# k26_baseboard_telemetry_extconn.net
KiCad netlist of a schematic drawn in Altium Designer
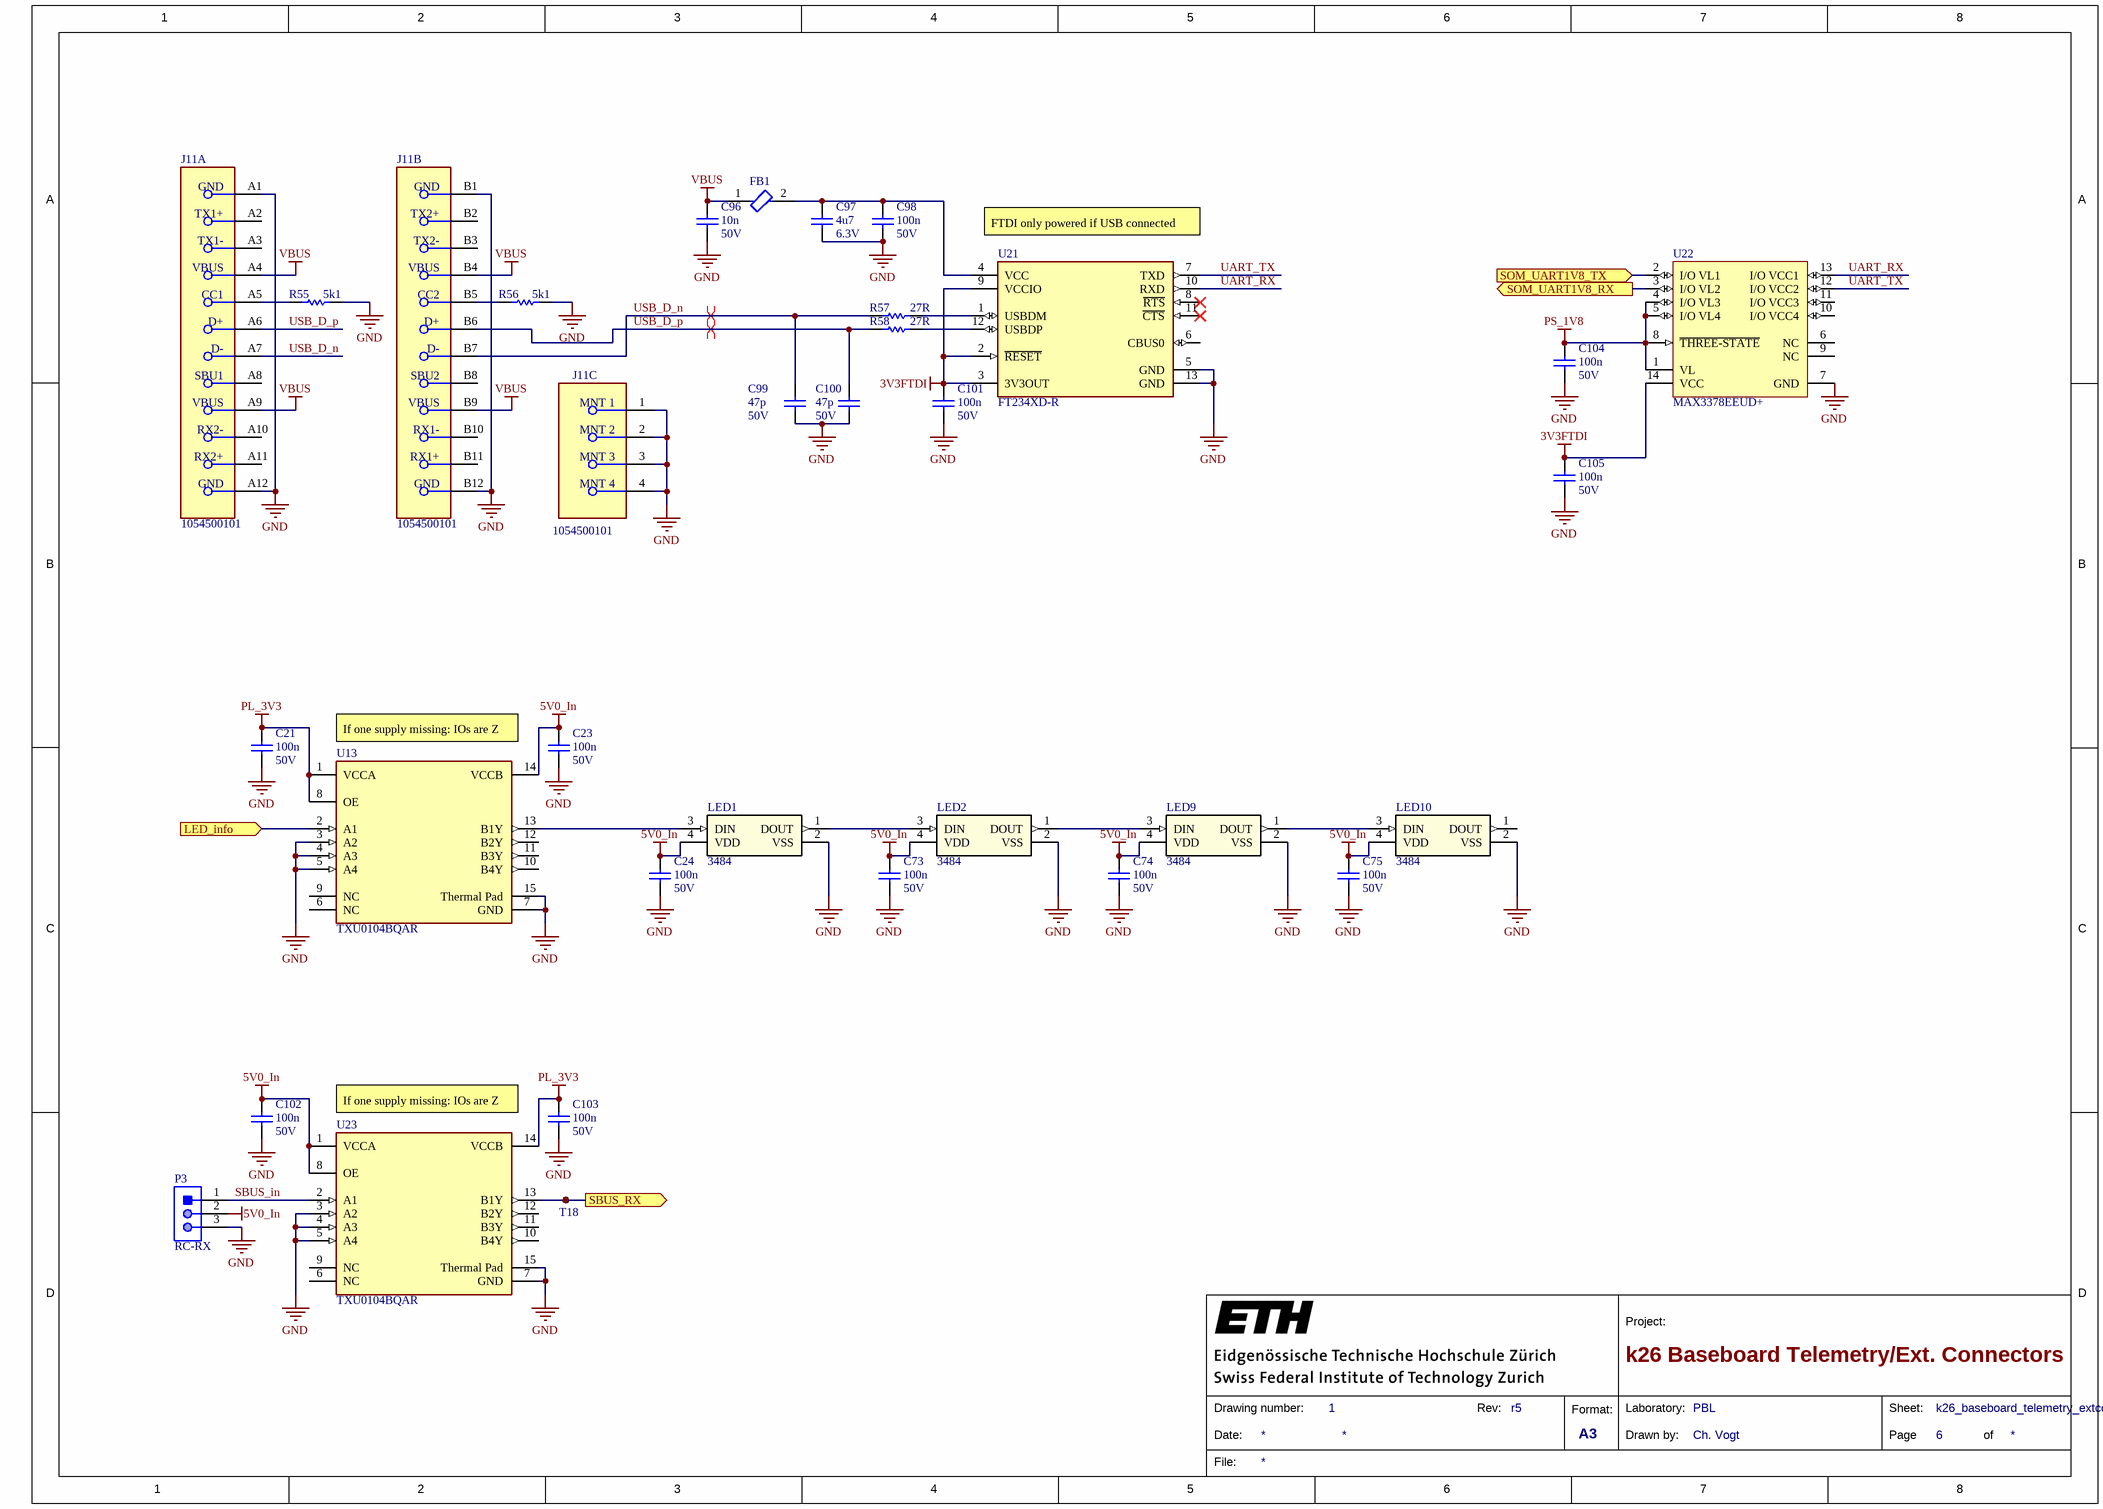
[diagram p0: k26_baseboard_telemetry_extconn.SchDoc]

(export (version "E")
  (design (tool "Eeschema 10.0.6"))
  (components
    (comp (ref "C21")
      (value "100n")
      (footprint "k26_FPGA_drone_baseboard:CAPC0402")
      (fields
        (field (name "MANUFACTURER") "Yageo")
        (field (name "MANUFACTURER PART NUMBER") "CC0402KRX5R9BB104")
        (field (name "RATED DC VOLTAGE (URDC)") "50V")
      )
      (libsource (lib "k26_FPGA_drone_baseboard") (part "cap0402"))
    )
    (comp (ref "C23")
      (value "100n")
      (footprint "k26_FPGA_drone_baseboard:CAPC0402")
      (fields
        (field (name "MANUFACTURER") "Yageo")
        (field (name "MANUFACTURER PART NUMBER") "CC0402KRX5R9BB104")
        (field (name "RATED DC VOLTAGE (URDC)") "50V")
      )
      (libsource (lib "k26_FPGA_drone_baseboard") (part "cap0402"))
    )
    (comp (ref "C24")
      (value "100n")
      (footprint "k26_FPGA_drone_baseboard:CAPC0402")
      (fields
        (field (name "MANUFACTURER") "Yageo")
        (field (name "MANUFACTURER PART NUMBER") "CC0402KRX5R9BB104")
        (field (name "RATED DC VOLTAGE (URDC)") "50V")
      )
      (libsource (lib "k26_FPGA_drone_baseboard") (part "cap0402"))
    )
    (comp (ref "C73")
      (value "100n")
      (footprint "k26_FPGA_drone_baseboard:CAPC0402")
      (fields
        (field (name "MANUFACTURER") "Yageo")
        (field (name "MANUFACTURER PART NUMBER") "CC0402KRX5R9BB104")
        (field (name "RATED DC VOLTAGE (URDC)") "50V")
      )
      (libsource (lib "k26_FPGA_drone_baseboard") (part "cap0402"))
    )
    (comp (ref "C74")
      (value "100n")
      (footprint "k26_FPGA_drone_baseboard:CAPC0402")
      (fields
        (field (name "MANUFACTURER") "Yageo")
        (field (name "MANUFACTURER PART NUMBER") "CC0402KRX5R9BB104")
        (field (name "RATED DC VOLTAGE (URDC)") "50V")
      )
      (libsource (lib "k26_FPGA_drone_baseboard") (part "cap0402"))
    )
    (comp (ref "C75")
      (value "100n")
      (footprint "k26_FPGA_drone_baseboard:CAPC0402")
      (fields
        (field (name "MANUFACTURER") "Yageo")
        (field (name "MANUFACTURER PART NUMBER") "CC0402KRX5R9BB104")
        (field (name "RATED DC VOLTAGE (URDC)") "50V")
      )
      (libsource (lib "k26_FPGA_drone_baseboard") (part "cap0402"))
    )
    (comp (ref "C96")
      (value "10n")
      (footprint "k26_FPGA_drone_baseboard:CAPC0402")
      (fields
        (field (name "MANUFACTURER") "Samsung")
        (field (name "MANUFACTURER PART NUMBER") "CL05B103KB5NNNC")
        (field (name "RATED DC VOLTAGE (URDC)") "50V")
      )
      (libsource (lib "k26_FPGA_drone_baseboard") (part "cap0402"))
    )
    (comp (ref "C97")
      (value "4u7")
      (footprint "k26_FPGA_drone_baseboard:CAPC0402")
      (fields
        (field (name "MANUFACTURER") "Murata")
        (field (name "MANUFACTURER PART NUMBER") "GRM155R60J475ME47D")
        (field (name "RATED DC VOLTAGE (URDC)") "6.3V")
      )
      (libsource (lib "k26_FPGA_drone_baseboard") (part "cap0402"))
    )
    (comp (ref "C98")
      (value "100n")
      (footprint "k26_FPGA_drone_baseboard:CAPC0402")
      (fields
        (field (name "MANUFACTURER") "Yageo")
        (field (name "MANUFACTURER PART NUMBER") "CC0402KRX5R9BB104")
        (field (name "RATED DC VOLTAGE (URDC)") "50V")
      )
      (libsource (lib "k26_FPGA_drone_baseboard") (part "cap0402"))
    )
    (comp (ref "C99")
      (value "47p")
      (footprint "k26_FPGA_drone_baseboard:CAPC0402")
      (fields
        (field (name "MANUFACTURER") "Murata")
        (field (name "MANUFACTURER PART NUMBER") "GRM1555C1H470JZ01D")
        (field (name "RATED DC VOLTAGE (URDC)") "50V")
      )
      (libsource (lib "k26_FPGA_drone_baseboard") (part "cap0402"))
    )
    (comp (ref "C100")
      (value "47p")
      (footprint "k26_FPGA_drone_baseboard:CAPC0402")
      (fields
        (field (name "MANUFACTURER") "Murata")
        (field (name "MANUFACTURER PART NUMBER") "GRM1555C1H470JZ01D")
        (field (name "RATED DC VOLTAGE (URDC)") "50V")
      )
      (libsource (lib "k26_FPGA_drone_baseboard") (part "cap0402"))
    )
    (comp (ref "C101")
      (value "100n")
      (footprint "k26_FPGA_drone_baseboard:CAPC0402")
      (fields
        (field (name "MANUFACTURER") "Yageo")
        (field (name "MANUFACTURER PART NUMBER") "CC0402KRX5R9BB104")
        (field (name "RATED DC VOLTAGE (URDC)") "50V")
      )
      (libsource (lib "k26_FPGA_drone_baseboard") (part "cap0402"))
    )
    (comp (ref "C102")
      (value "100n")
      (footprint "k26_FPGA_drone_baseboard:CAPC0402")
      (fields
        (field (name "MANUFACTURER") "Yageo")
        (field (name "MANUFACTURER PART NUMBER") "CC0402KRX5R9BB104")
        (field (name "RATED DC VOLTAGE (URDC)") "50V")
      )
      (libsource (lib "k26_FPGA_drone_baseboard") (part "cap0402"))
    )
    (comp (ref "C103")
      (value "100n")
      (footprint "k26_FPGA_drone_baseboard:CAPC0402")
      (fields
        (field (name "MANUFACTURER") "Yageo")
        (field (name "MANUFACTURER PART NUMBER") "CC0402KRX5R9BB104")
        (field (name "RATED DC VOLTAGE (URDC)") "50V")
      )
      (libsource (lib "k26_FPGA_drone_baseboard") (part "cap0402"))
    )
    (comp (ref "C104")
      (value "100n")
      (footprint "k26_FPGA_drone_baseboard:CAPC0402")
      (fields
        (field (name "MANUFACTURER") "Yageo")
        (field (name "MANUFACTURER PART NUMBER") "CC0402KRX5R9BB104")
        (field (name "RATED DC VOLTAGE (URDC)") "50V")
      )
      (libsource (lib "k26_FPGA_drone_baseboard") (part "cap0402"))
    )
    (comp (ref "C105")
      (value "100n")
      (footprint "k26_FPGA_drone_baseboard:CAPC0402")
      (fields
        (field (name "MANUFACTURER") "Yageo")
        (field (name "MANUFACTURER PART NUMBER") "CC0402KRX5R9BB104")
        (field (name "RATED DC VOLTAGE (URDC)") "50V")
      )
      (libsource (lib "k26_FPGA_drone_baseboard") (part "cap0402"))
    )
    (comp (ref "FB1")
      (value "BLM18PG600SN1D")
      (footprint "FP-BLM18-0_15-t0_8-MFG")
      (description "Chip Ferrite Bead, 0603, 60Ω @ 100MHz, 0.1Ω, , 1A")
      (fields (field (name "TOLERANCE") "25%") (field (name "MANUFACTURER") "Murata"))
      (libsource (lib "k26_FPGA_drone_baseboard") (part "CMP-0686-00575-3"))
    )
    (comp (ref "J11")
      (value "1054500101")
      (footprint "k26_FPGA_drone_baseboard:FP-1054500101-MFG")
      (description "CONN RCP USB3.1 TYPEC 24P SMD RA")
      (fields
        (field (name "MANUFACTURER") "Molex")
        (field (name "OCTOPART") "https://octopart.com/105450-0101-molex-68082325")
      )
      (libsource (lib "k26_FPGA_drone_baseboard") (part "CONN RCP USB3.1"))
    )
    (comp (ref "LED1")
      (value "3484")
      (footprint "3484_ADA-L")
      (description "No Description Available")
      (fields (field (name "COPYRIGHT") "Copyright (C) 2024 Ultra Librarian. All rights reserved."))
      (libsource (lib "k26_FPGA_drone_baseboard") (part "3484"))
    )
    (comp (ref "LED2")
      (value "3484")
      (footprint "3484_ADA-L")
      (description "No Description Available")
      (fields (field (name "COPYRIGHT") "Copyright (C) 2024 Ultra Librarian. All rights reserved."))
      (libsource (lib "k26_FPGA_drone_baseboard") (part "3484"))
    )
    (comp (ref "LED9")
      (value "3484")
      (footprint "3484_ADA-L")
      (description "No Description Available")
      (fields (field (name "COPYRIGHT") "Copyright (C) 2024 Ultra Librarian. All rights reserved."))
      (libsource (lib "k26_FPGA_drone_baseboard") (part "3484"))
    )
    (comp (ref "LED10")
      (value "3484")
      (footprint "3484_ADA-L")
      (description "No Description Available")
      (fields (field (name "COPYRIGHT") "Copyright (C) 2024 Ultra Librarian. All rights reserved."))
      (libsource (lib "k26_FPGA_drone_baseboard") (part "3484"))
    )
    (comp (ref "P3")
      (value "RC-RX")
      (footprint "MOLX-22-28-4033_V")
      (description "Male Header, Pitch 2.54 mm, 1 x 3 Position, Height 8.38 mm, Tail Length 3.18 mm, RoHS, Bulk")
      (fields (field (name "MANUFACTURER") "Molex") (field (name "MANUFACTURER PART NUMBER") "22-28-4033"))
      (libsource (lib "k26_FPGA_drone_baseboard") (part "CMP-1676-00001-5"))
    )
    (comp (ref "R55")
      (value "5k1")
      (footprint "k26_FPGA_drone_baseboard:RES0402")
      (fields
        (field (name "MANUFACTURER") "Yageo")
        (field (name "MANUFACTURER PART NUMBER") "RC0402FR-075K1L")
        (field (name "TOLERANCE") "1%")
      )
      (libsource (lib "k26_FPGA_drone_baseboard") (part "res0402"))
    )
    (comp (ref "R56")
      (value "5k1")
      (footprint "k26_FPGA_drone_baseboard:RES0402")
      (fields
        (field (name "MANUFACTURER") "Yageo")
        (field (name "MANUFACTURER PART NUMBER") "RC0402FR-075K1L")
        (field (name "TOLERANCE") "1%")
      )
      (libsource (lib "k26_FPGA_drone_baseboard") (part "res0402"))
    )
    (comp (ref "R57")
      (value "27R")
      (footprint "k26_FPGA_drone_baseboard:RES0402")
      (fields
        (field (name "MANUFACTURER") "Panasonic")
        (field (name "MANUFACTURER PART NUMBER") "ERJ-2RKF27R0X")
        (field (name "TOLERANCE") "1%")
      )
      (libsource (lib "k26_FPGA_drone_baseboard") (part "res0402"))
    )
    (comp (ref "R58")
      (value "27R")
      (footprint "k26_FPGA_drone_baseboard:RES0402")
      (fields
        (field (name "MANUFACTURER") "Panasonic")
        (field (name "MANUFACTURER PART NUMBER") "ERJ-2RKF27R0X")
        (field (name "TOLERANCE") "1%")
      )
      (libsource (lib "k26_FPGA_drone_baseboard") (part "res0402"))
    )
    (comp (ref "T18")
      (value "CMP-01283-1")
      (footprint "Pad-1mm")
      (description "1mm SMT Test Pad")
      (libsource (lib "k26_FPGA_drone_baseboard") (part "CMP-01283-1"))
    )
    (comp (ref "U13")
      (value "TXU0104BQAR")
      (footprint "FP-BQA0014A-MFG")
      (description "FOUR CHANNEL UNIDIRECTIONAL LEVE")
      (fields (field (name "MANUFACTURER") "Texas Instruments"))
      (libsource (lib "k26_FPGA_drone_baseboard") (part "CMP-04899-000128-1"))
    )
    (comp (ref "U21")
      (value "FT234XD-R")
      (footprint "FP-DFN-12-IPC_B")
      (description "IC USB SERIAL BASIC UART 12DFN")
      (fields (field (name "MANUFACTURER") "FTDI"))
      (libsource (lib "k26_FPGA_drone_baseboard") (part "CMP-0248-00027-3"))
    )
    (comp (ref "U22")
      (value "MAX3378EEUD+")
      (footprint "MAXM-U14+1_V")
      (fields (field (name "MANUFACTURER") "Maxim"))
      (libsource (lib "k26_FPGA_drone_baseboard") (part "CMP-1703-00001-3"))
    )
    (comp (ref "U23")
      (value "TXU0104BQAR")
      (footprint "FP-BQA0014A-MFG")
      (description "FOUR CHANNEL UNIDIRECTIONAL LEVE")
      (fields (field (name "MANUFACTURER") "Texas Instruments"))
      (libsource (lib "k26_FPGA_drone_baseboard") (part "CMP-04899-000128-1"))
    )
  )
  (nets
    (net (code "1") (name "/LED_info") (class "Default")
      (node (ref "U13") (pin "2") (pinfunction "A1_2") (pintype "input"))
    )
    (net (code "2") (name "/SBUS_RX") (class "Default")
      (node (ref "T18") (pin "1") (pinfunction "1_1") (pintype "passive"))
      (node (ref "U23") (pin "13") (pinfunction "B1Y_13") (pintype "output"))
    )
    (net (code "3") (name "/SBUS_in") (class "Default")
      (node (ref "P3") (pin "1") (pinfunction "1_1") (pintype "passive"))
      (node (ref "U23") (pin "2") (pinfunction "A1_2") (pintype "input"))
    )
    (net (code "4") (name "/SOM_UART1V8_RX") (class "Default")
      (node (ref "U22") (pin "3") (pinfunction "I/O_VL2_3") (pintype "bidirectional"))
    )
    (net (code "5") (name "/SOM_UART1V8_TX") (class "Default")
      (node (ref "U22") (pin "2") (pinfunction "I/O_VL1_2") (pintype "bidirectional"))
    )
    (net (code "6") (name "/UART_RX") (class "Default")
      (node (ref "U21") (pin "10") (pinfunction "RXD_10") (pintype "output"))
      (node (ref "U22") (pin "13") (pinfunction "I/O_VCC1_13") (pintype "bidirectional"))
    )
    (net (code "7") (name "/UART_TX") (class "Default")
      (node (ref "U21") (pin "7") (pinfunction "TXD_7") (pintype "output"))
      (node (ref "U22") (pin "12") (pinfunction "I/O_VCC2_12") (pintype "bidirectional"))
    )
    (net (code "8") (name "/USB_D_n") (class "Default")
      (node (ref "C99") (pin "2") (pinfunction "2_2") (pintype "passive"))
      (node (ref "J11") (pin "A7") (pinfunction "D-_A7") (pintype "passive"))
      (node (ref "J11") (pin "B7") (pinfunction "D-_B7") (pintype "passive"))
      (node (ref "R57") (pin "1") (pinfunction "1_1") (pintype "passive"))
    )
    (net (code "9") (name "/USB_D_p") (class "Default")
      (node (ref "C100") (pin "2") (pinfunction "2_2") (pintype "passive"))
      (node (ref "J11") (pin "A6") (pinfunction "D+_A6") (pintype "passive"))
      (node (ref "J11") (pin "B6") (pinfunction "D+_B6") (pintype "passive"))
      (node (ref "R58") (pin "1") (pinfunction "1_1") (pintype "passive"))
    )
    (net (code "10") (name "3V3FTDI") (class "Default")
      (node (ref "C101") (pin "2") (pinfunction "2_2") (pintype "passive"))
      (node (ref "C105") (pin "2") (pinfunction "2_2") (pintype "passive"))
      (node (ref "U21") (pin "2") (pinfunction "~{RESET}_2") (pintype "input"))
      (node (ref "U21") (pin "3") (pinfunction "3V3OUT_3") (pintype "power_in"))
      (node (ref "U21") (pin "9") (pinfunction "VCCIO_9") (pintype "power_in"))
      (node (ref "U22") (pin "14") (pinfunction "VCC_14") (pintype "power_in"))
    )
    (net (code "11") (name "5V0_In") (class "Default")
      (node (ref "C102") (pin "2") (pinfunction "2_2") (pintype "passive"))
      (node (ref "C23") (pin "2") (pinfunction "2_2") (pintype "passive"))
      (node (ref "C24") (pin "2") (pinfunction "2_2") (pintype "passive"))
      (node (ref "C73") (pin "2") (pinfunction "2_2") (pintype "passive"))
      (node (ref "C74") (pin "2") (pinfunction "2_2") (pintype "passive"))
      (node (ref "C75") (pin "2") (pinfunction "2_2") (pintype "passive"))
      (node (ref "LED1") (pin "4") (pinfunction "VDD_4") (pintype "power_in"))
      (node (ref "LED10") (pin "4") (pinfunction "VDD_4") (pintype "power_in"))
      (node (ref "LED2") (pin "4") (pinfunction "VDD_4") (pintype "power_in"))
      (node (ref "LED9") (pin "4") (pinfunction "VDD_4") (pintype "power_in"))
      (node (ref "P3") (pin "2") (pinfunction "2_2") (pintype "passive"))
      (node (ref "U13") (pin "14") (pinfunction "VCCB_14") (pintype "power_in"))
      (node (ref "U23") (pin "1") (pinfunction "VCCA_1") (pintype "power_in"))
      (node (ref "U23") (pin "8") (pinfunction "OE_8") (pintype "passive"))
    )
    (net (code "12") (name "GND") (class "Default")
      (node (ref "C100") (pin "1") (pinfunction "1_1") (pintype "passive"))
      (node (ref "C101") (pin "1") (pinfunction "1_1") (pintype "passive"))
      (node (ref "C102") (pin "1") (pinfunction "1_1") (pintype "passive"))
      (node (ref "C103") (pin "1") (pinfunction "1_1") (pintype "passive"))
      (node (ref "C104") (pin "1") (pinfunction "1_1") (pintype "passive"))
      (node (ref "C105") (pin "1") (pinfunction "1_1") (pintype "passive"))
      (node (ref "C21") (pin "1") (pinfunction "1_1") (pintype "passive"))
      (node (ref "C23") (pin "1") (pinfunction "1_1") (pintype "passive"))
      (node (ref "C24") (pin "1") (pinfunction "1_1") (pintype "passive"))
      (node (ref "C73") (pin "1") (pinfunction "1_1") (pintype "passive"))
      (node (ref "C74") (pin "1") (pinfunction "1_1") (pintype "passive"))
      (node (ref "C75") (pin "1") (pinfunction "1_1") (pintype "passive"))
      (node (ref "C96") (pin "1") (pinfunction "1_1") (pintype "passive"))
      (node (ref "C97") (pin "1") (pinfunction "1_1") (pintype "passive"))
      (node (ref "C98") (pin "1") (pinfunction "1_1") (pintype "passive"))
      (node (ref "C99") (pin "1") (pinfunction "1_1") (pintype "passive"))
      (node (ref "J11") (pin "1") (pinfunction "MNT_1_1") (pintype "passive"))
      (node (ref "J11") (pin "2") (pinfunction "MNT_2_2") (pintype "passive"))
      (node (ref "J11") (pin "3") (pinfunction "MNT_3_3") (pintype "passive"))
      (node (ref "J11") (pin "4") (pinfunction "MNT_4_4") (pintype "passive"))
      (node (ref "J11") (pin "A1") (pinfunction "GND_A1") (pintype "passive"))
      (node (ref "J11") (pin "A12") (pinfunction "GND_A12") (pintype "passive"))
      (node (ref "J11") (pin "B1") (pinfunction "GND_B1") (pintype "passive"))
      (node (ref "J11") (pin "B12") (pinfunction "GND_B12") (pintype "passive"))
      (node (ref "LED1") (pin "2") (pinfunction "VSS_2") (pintype "power_in"))
      (node (ref "LED10") (pin "2") (pinfunction "VSS_2") (pintype "power_in"))
      (node (ref "LED2") (pin "2") (pinfunction "VSS_2") (pintype "power_in"))
      (node (ref "LED9") (pin "2") (pinfunction "VSS_2") (pintype "power_in"))
      (node (ref "P3") (pin "3") (pinfunction "3_3") (pintype "passive"))
      (node (ref "R55") (pin "1") (pinfunction "1_1") (pintype "passive"))
      (node (ref "R56") (pin "1") (pinfunction "1_1") (pintype "passive"))
      (node (ref "U13") (pin "15") (pinfunction "Thermal_Pad_15") (pintype "power_in"))
      (node (ref "U13") (pin "3") (pinfunction "A2_3") (pintype "input"))
      (node (ref "U13") (pin "4") (pinfunction "A3_4") (pintype "input"))
      (node (ref "U13") (pin "5") (pinfunction "A4_5") (pintype "input"))
      (node (ref "U13") (pin "7") (pinfunction "GND_7") (pintype "power_in"))
      (node (ref "U21") (pin "13") (pinfunction "GND_13") (pintype "power_in"))
      (node (ref "U21") (pin "5") (pinfunction "GND_5") (pintype "power_in"))
      (node (ref "U22") (pin "7") (pinfunction "GND_7") (pintype "power_in"))
      (node (ref "U23") (pin "15") (pinfunction "Thermal_Pad_15") (pintype "power_in"))
      (node (ref "U23") (pin "3") (pinfunction "A2_3") (pintype "input"))
      (node (ref "U23") (pin "4") (pinfunction "A3_4") (pintype "input"))
      (node (ref "U23") (pin "5") (pinfunction "A4_5") (pintype "input"))
      (node (ref "U23") (pin "7") (pinfunction "GND_7") (pintype "power_in"))
    )
    (net (code "13") (name "Net-(J11A-CC1)") (class "Default")
      (node (ref "J11") (pin "A5") (pinfunction "CC1_A5") (pintype "passive"))
      (node (ref "R55") (pin "2") (pinfunction "2_2") (pintype "passive"))
    )
    (net (code "14") (name "Net-(J11B-CC2)") (class "Default")
      (node (ref "J11") (pin "B5") (pinfunction "CC2_B5") (pintype "passive"))
      (node (ref "R56") (pin "2") (pinfunction "2_2") (pintype "passive"))
    )
    (net (code "15") (name "Net-(LED1-DIN)") (class "Default")
      (node (ref "LED1") (pin "3") (pinfunction "DIN_3") (pintype "input"))
      (node (ref "U13") (pin "13") (pinfunction "B1Y_13") (pintype "output"))
    )
    (net (code "16") (name "Net-(LED1-DOUT)") (class "Default")
      (node (ref "LED1") (pin "1") (pinfunction "DOUT_1") (pintype "output"))
      (node (ref "LED2") (pin "3") (pinfunction "DIN_3") (pintype "input"))
    )
    (net (code "17") (name "Net-(LED2-DOUT)") (class "Default")
      (node (ref "LED2") (pin "1") (pinfunction "DOUT_1") (pintype "output"))
      (node (ref "LED9") (pin "3") (pinfunction "DIN_3") (pintype "input"))
    )
    (net (code "18") (name "Net-(LED10-DIN)") (class "Default")
      (node (ref "LED10") (pin "3") (pinfunction "DIN_3") (pintype "input"))
      (node (ref "LED9") (pin "1") (pinfunction "DOUT_1") (pintype "output"))
    )
    (net (code "19") (name "Net-(U21-USBDM)") (class "Default")
      (node (ref "R57") (pin "2") (pinfunction "2_2") (pintype "passive"))
      (node (ref "U21") (pin "1") (pinfunction "USBDM_1") (pintype "bidirectional"))
    )
    (net (code "20") (name "Net-(U21-USBDP)") (class "Default")
      (node (ref "R58") (pin "2") (pinfunction "2_2") (pintype "passive"))
      (node (ref "U21") (pin "12") (pinfunction "USBDP_12") (pintype "bidirectional"))
    )
    (net (code "21") (name "Net-(U21-VCC)") (class "Default")
      (node (ref "C97") (pin "2") (pinfunction "2_2") (pintype "passive"))
      (node (ref "C98") (pin "2") (pinfunction "2_2") (pintype "passive"))
      (node (ref "FB1") (pin "2") (pinfunction "2_2") (pintype "passive"))
      (node (ref "U21") (pin "4") (pinfunction "VCC_4") (pintype "power_in"))
    )
    (net (code "22") (name "PL_3V3") (class "Default")
      (node (ref "C103") (pin "2") (pinfunction "2_2") (pintype "passive"))
      (node (ref "C21") (pin "2") (pinfunction "2_2") (pintype "passive"))
      (node (ref "U13") (pin "1") (pinfunction "VCCA_1") (pintype "power_in"))
      (node (ref "U13") (pin "8") (pinfunction "OE_8") (pintype "passive"))
      (node (ref "U23") (pin "14") (pinfunction "VCCB_14") (pintype "power_in"))
    )
    (net (code "23") (name "PS_1V8") (class "Default")
      (node (ref "C104") (pin "2") (pinfunction "2_2") (pintype "passive"))
      (node (ref "U22") (pin "1") (pinfunction "VL_1") (pintype "power_in"))
      (node (ref "U22") (pin "4") (pinfunction "I/O_VL3_4") (pintype "bidirectional"))
      (node (ref "U22") (pin "5") (pinfunction "I/O_VL4_5") (pintype "bidirectional"))
      (node (ref "U22") (pin "8") (pinfunction "~{THREE-STATE}_8") (pintype "input"))
    )
    (net (code "24") (name "VBUS") (class "Default")
      (node (ref "C96") (pin "2") (pinfunction "2_2") (pintype "passive"))
      (node (ref "FB1") (pin "1") (pinfunction "1_1") (pintype "passive"))
      (node (ref "J11") (pin "A4") (pinfunction "VBUS_A4") (pintype "passive"))
      (node (ref "J11") (pin "A9") (pinfunction "VBUS_A9") (pintype "passive"))
      (node (ref "J11") (pin "B4") (pinfunction "VBUS_B4") (pintype "passive"))
      (node (ref "J11") (pin "B9") (pinfunction "VBUS_B9") (pintype "passive"))
    )
    (net (code "25") (name "unconnected-(J11A-RX2+-PadA11)") (class "Default")
      (node (ref "J11") (pin "A11") (pinfunction "RX2+_A11") (pintype "passive"))
    )
    (net (code "26") (name "unconnected-(J11A-RX2--PadA10)") (class "Default")
      (node (ref "J11") (pin "A10") (pinfunction "RX2-_A10") (pintype "passive"))
    )
    (net (code "27") (name "unconnected-(J11A-SBU1-PadA8)") (class "Default")
      (node (ref "J11") (pin "A8") (pinfunction "SBU1_A8") (pintype "passive"))
    )
    (net (code "28") (name "unconnected-(J11A-TX1+-PadA2)") (class "Default")
      (node (ref "J11") (pin "A2") (pinfunction "TX1+_A2") (pintype "passive"))
    )
    (net (code "29") (name "unconnected-(J11A-TX1--PadA3)") (class "Default")
      (node (ref "J11") (pin "A3") (pinfunction "TX1-_A3") (pintype "passive"))
    )
    (net (code "30") (name "unconnected-(J11B-RX1+-PadB11)") (class "Default")
      (node (ref "J11") (pin "B11") (pinfunction "RX1+_B11") (pintype "passive"))
    )
    (net (code "31") (name "unconnected-(J11B-RX1--PadB10)") (class "Default")
      (node (ref "J11") (pin "B10") (pinfunction "RX1-_B10") (pintype "passive"))
    )
    (net (code "32") (name "unconnected-(J11B-SBU2-PadB8)") (class "Default")
      (node (ref "J11") (pin "B8") (pinfunction "SBU2_B8") (pintype "passive"))
    )
    (net (code "33") (name "unconnected-(J11B-TX2+-PadB2)") (class "Default")
      (node (ref "J11") (pin "B2") (pinfunction "TX2+_B2") (pintype "passive"))
    )
    (net (code "34") (name "unconnected-(J11B-TX2--PadB3)") (class "Default")
      (node (ref "J11") (pin "B3") (pinfunction "TX2-_B3") (pintype "passive"))
    )
    (net (code "35") (name "unconnected-(LED10-DOUT-Pad1)") (class "Default")
      (node (ref "LED10") (pin "1") (pinfunction "DOUT_1") (pintype "output"))
    )
    (net (code "36") (name "unconnected-(U13-B2Y-Pad12)") (class "Default")
      (node (ref "U13") (pin "12") (pinfunction "B2Y_12") (pintype "output"))
    )
    (net (code "37") (name "unconnected-(U13-B3Y-Pad11)") (class "Default")
      (node (ref "U13") (pin "11") (pinfunction "B3Y_11") (pintype "output"))
    )
    (net (code "38") (name "unconnected-(U13-B4Y-Pad10)") (class "Default")
      (node (ref "U13") (pin "10") (pinfunction "B4Y_10") (pintype "output"))
    )
    (net (code "39") (name "unconnected-(U13-NC-Pad6)") (class "Default")
      (node (ref "U13") (pin "6") (pinfunction "NC_6") (pintype "passive"))
    )
    (net (code "40") (name "unconnected-(U13-NC-Pad9)") (class "Default")
      (node (ref "U13") (pin "9") (pinfunction "NC_9") (pintype "passive"))
    )
    (net (code "41") (name "unconnected-(U21-CBUS0-Pad6)") (class "Default")
      (node (ref "U21") (pin "6") (pinfunction "CBUS0_6") (pintype "bidirectional"))
    )
    (net (code "42") (name "unconnected-(U21-~{CTS}-Pad11)") (class "Default")
      (node (ref "U21") (pin "11") (pinfunction "~{CTS}_11") (pintype "input+no_connect"))
    )
    (net (code "43") (name "unconnected-(U21-~{RTS}-Pad8)") (class "Default")
      (node (ref "U21") (pin "8") (pinfunction "~{RTS}_8") (pintype "input+no_connect"))
    )
    (net (code "44") (name "unconnected-(U22-I{slash}O_VCC3-Pad11)") (class "Default")
      (node (ref "U22") (pin "11") (pinfunction "I/O_VCC3_11") (pintype "bidirectional"))
    )
    (net (code "45") (name "unconnected-(U22-I{slash}O_VCC4-Pad10)") (class "Default")
      (node (ref "U22") (pin "10") (pinfunction "I/O_VCC4_10") (pintype "bidirectional"))
    )
    (net (code "46") (name "unconnected-(U22-NC-Pad6)") (class "Default")
      (node (ref "U22") (pin "6") (pinfunction "NC_6") (pintype "passive"))
    )
    (net (code "47") (name "unconnected-(U22-NC-Pad9)") (class "Default")
      (node (ref "U22") (pin "9") (pinfunction "NC_9") (pintype "passive"))
    )
    (net (code "48") (name "unconnected-(U23-B2Y-Pad12)") (class "Default")
      (node (ref "U23") (pin "12") (pinfunction "B2Y_12") (pintype "output"))
    )
    (net (code "49") (name "unconnected-(U23-B3Y-Pad11)") (class "Default")
      (node (ref "U23") (pin "11") (pinfunction "B3Y_11") (pintype "output"))
    )
    (net (code "50") (name "unconnected-(U23-B4Y-Pad10)") (class "Default")
      (node (ref "U23") (pin "10") (pinfunction "B4Y_10") (pintype "output"))
    )
    (net (code "51") (name "unconnected-(U23-NC-Pad6)") (class "Default")
      (node (ref "U23") (pin "6") (pinfunction "NC_6") (pintype "passive"))
    )
    (net (code "52") (name "unconnected-(U23-NC-Pad9)") (class "Default")
      (node (ref "U23") (pin "9") (pinfunction "NC_9") (pintype "passive"))
    )
  )
)
